# ESP32_EVKIT_v1_0.net
KiCad netlist of a schematic drawn in EAGLE
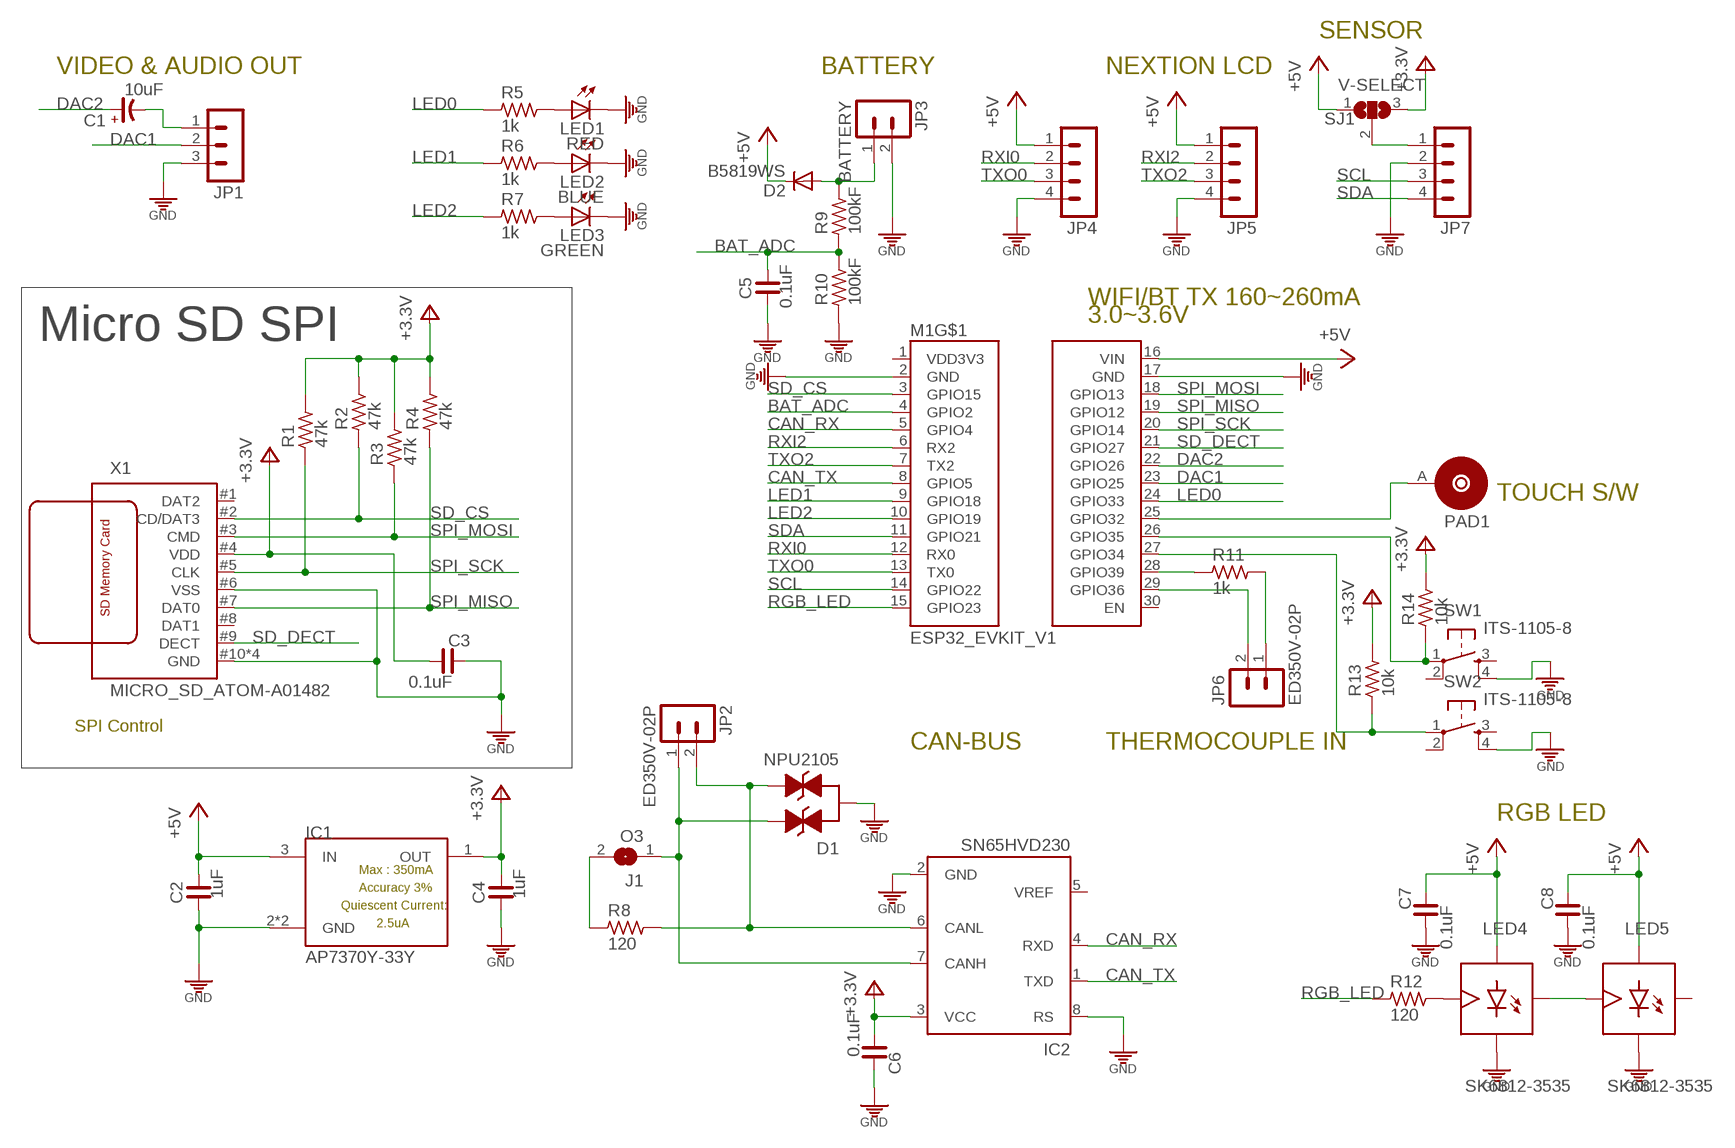
[diagram p0: schematic, sheet 1]

(export (version "E")
  (design (tool "Eeschema 10.0.6"))
  (components
    (comp (ref "C1")
      (value "10uF")
      (footprint "eagle-import:C2012_T")
      (libsource (lib "eagle-import") (part "CP_2012"))
    )
    (comp (ref "C2")
      (value "1uF")
      (footprint "eagle-import:C0603")
      (libsource (lib "eagle-import") (part "C_0603"))
    )
    (comp (ref "C3")
      (value "0.1uF")
      (footprint "eagle-import:C0603")
      (libsource (lib "eagle-import") (part "C_0603"))
    )
    (comp (ref "C4")
      (value "1uF")
      (footprint "eagle-import:C0603")
      (libsource (lib "eagle-import") (part "C_0603"))
    )
    (comp (ref "C5")
      (value "0.1uF")
      (footprint "eagle-import:C0603")
      (libsource (lib "eagle-import") (part "C_0603"))
    )
    (comp (ref "C6")
      (value "0.1uF")
      (footprint "eagle-import:C0603")
      (libsource (lib "eagle-import") (part "C_0603"))
    )
    (comp (ref "C7")
      (value "0.1uF")
      (footprint "eagle-import:C0603")
      (libsource (lib "eagle-import") (part "C_0603"))
    )
    (comp (ref "C8")
      (value "0.1uF")
      (footprint "eagle-import:C0603")
      (libsource (lib "eagle-import") (part "C_0603"))
    )
    (comp (ref "D1")
      (value "NPU2105")
      (footprint "eagle-import:SOT23@2")
      (libsource (lib "eagle-import") (part "NPU2105"))
    )
    (comp (ref "D2")
      (value "B5819WS")
      (footprint "eagle-import:SOD323-W")
      (libsource (lib "eagle-import") (part "B5189WWS"))
    )
    (comp (ref "IC1")
      (value "AP7370Y-33Y")
      (footprint "eagle-import:SOT89")
      (libsource (lib "eagle-import") (part "AP7370Y"))
    )
    (comp (ref "IC2")
      (value "SN65HVD230")
      (footprint "eagle-import:SO8")
      (libsource (lib "eagle-import") (part "PCA82C250T"))
    )
    (comp (ref "J1") (value "O3") (footprint "eagle-import:SJ") (libsource (lib "eagle-import") (part "SJ")))
    (comp (ref "JP1")
      (value "MA03-1DEF")
      (footprint "eagle-import:MA03")
      (libsource (lib "eagle-import") (part "MA03-1DEF"))
    )
    (comp (ref "JP2")
      (value "ED350V-02P")
      (footprint "eagle-import:ED350V-02P")
      (libsource (lib "eagle-import") (part "MA02ED350V-02P"))
    )
    (comp (ref "JP3")
      (value "BATTERY")
      (footprint "eagle-import:53398-02")
      (libsource (lib "eagle-import") (part "MA0253398"))
    )
    (comp (ref "JP4")
      (value "MA04-1SMALL")
      (footprint "eagle-import:MA04-1-S")
      (libsource (lib "eagle-import") (part "MA04-1SMALL"))
    )
    (comp (ref "JP5")
      (value "MA04-1SMALL")
      (footprint "eagle-import:MA04-1-S")
      (libsource (lib "eagle-import") (part "MA04-1SMALL"))
    )
    (comp (ref "JP6")
      (value "ED350V-02P")
      (footprint "eagle-import:ED350V-02P")
      (libsource (lib "eagle-import") (part "MA02ED350V-02P"))
    )
    (comp (ref "JP7")
      (value "MA04-1SMALL")
      (footprint "eagle-import:MA04-1-S")
      (libsource (lib "eagle-import") (part "MA04-1SMALL"))
    )
    (comp (ref "LED1")
      (value "RED")
      (footprint "eagle-import:LED-1608")
      (libsource (lib "eagle-import") (part "LEDSMD-1608"))
    )
    (comp (ref "LED2")
      (value "BLUE")
      (footprint "eagle-import:LED-1608")
      (libsource (lib "eagle-import") (part "LEDSMD-1608"))
    )
    (comp (ref "LED3")
      (value "GREEN")
      (footprint "eagle-import:LED-1608")
      (libsource (lib "eagle-import") (part "LEDSMD-1608"))
    )
    (comp (ref "LED4")
      (value "SK6812-3535")
      (footprint "eagle-import:LED3535")
      (libsource (lib "eagle-import") (part "SK68123535"))
    )
    (comp (ref "LED5")
      (value "SK6812-3535")
      (footprint "eagle-import:LED3535")
      (libsource (lib "eagle-import") (part "SK68123535"))
    )
    (comp (ref "M1")
      (value "ESP32_EVKIT_V1")
      (footprint "eagle-import:ESP32_DEVKIT_V1_DOIT")
      (libsource (lib "eagle-import") (part "ESP32_EVKIT_V1"))
    )
    (comp (ref "PAD1")
      (value "TOUCH_PAD01")
      (footprint "eagle-import:TOUCH_PAD1")
      (libsource (lib "eagle-import") (part "TOUCH_PAD01"))
    )
    (comp (ref "R1")
      (value "47k")
      (footprint "eagle-import:R0603")
      (libsource (lib "eagle-import") (part "R_0603"))
    )
    (comp (ref "R2")
      (value "47k")
      (footprint "eagle-import:R0603")
      (libsource (lib "eagle-import") (part "R_0603"))
    )
    (comp (ref "R3")
      (value "47k")
      (footprint "eagle-import:R0603")
      (libsource (lib "eagle-import") (part "R_0603"))
    )
    (comp (ref "R4")
      (value "47k")
      (footprint "eagle-import:R0603")
      (libsource (lib "eagle-import") (part "R_0603"))
    )
    (comp (ref "R5")
      (value "1k")
      (footprint "eagle-import:R0603")
      (libsource (lib "eagle-import") (part "R_0603"))
    )
    (comp (ref "R6")
      (value "1k")
      (footprint "eagle-import:R0603")
      (libsource (lib "eagle-import") (part "R_0603"))
    )
    (comp (ref "R7")
      (value "1k")
      (footprint "eagle-import:R0603")
      (libsource (lib "eagle-import") (part "R_0603"))
    )
    (comp (ref "R8")
      (value "120")
      (footprint "eagle-import:R0603")
      (libsource (lib "eagle-import") (part "R_0603"))
    )
    (comp (ref "R9")
      (value "100kF")
      (footprint "eagle-import:R0603")
      (libsource (lib "eagle-import") (part "R_0603"))
    )
    (comp (ref "R10")
      (value "100kF")
      (footprint "eagle-import:R0603")
      (libsource (lib "eagle-import") (part "R_0603"))
    )
    (comp (ref "R11")
      (value "1k")
      (footprint "eagle-import:R0603")
      (libsource (lib "eagle-import") (part "R_0603"))
    )
    (comp (ref "R12")
      (value "120")
      (footprint "eagle-import:R0603")
      (libsource (lib "eagle-import") (part "R_0603"))
    )
    (comp (ref "R13")
      (value "10k")
      (footprint "eagle-import:R0603")
      (libsource (lib "eagle-import") (part "R_0603"))
    )
    (comp (ref "R14")
      (value "10k")
      (footprint "eagle-import:R0603")
      (libsource (lib "eagle-import") (part "R_0603"))
    )
    (comp (ref "SJ1")
      (value "V-SELECT")
      (footprint "eagle-import:SJ_3")
      (libsource (lib "eagle-import") (part "SOLDERJUMPER_2WAYS"))
    )
    (comp (ref "SW1")
      (value "ITS-1105-8")
      (footprint "eagle-import:ITS-1105")
      (libsource (lib "eagle-import") (part "ITS-1105"))
    )
    (comp (ref "SW2")
      (value "ITS-1105-8")
      (footprint "eagle-import:ITS-1105")
      (libsource (lib "eagle-import") (part "ITS-1105"))
    )
    (comp (ref "X1")
      (value "MICRO_SD_ATOM-A01482")
      (footprint "eagle-import:ATOM-A01482")
      (libsource (lib "eagle-import") (part "MICRO_SD_ATOM-A01482"))
    )
  )
  (nets
    (net (code "1") (name "+3V3") (class "Default")
      (node (ref "C3") (pin "2") (pinfunction "2_2") (pintype "passive"))
      (node (ref "C4") (pin "1") (pinfunction "1_1") (pintype "passive"))
      (node (ref "C6") (pin "2") (pinfunction "2_2") (pintype "passive"))
      (node (ref "IC1") (pin "1") (pinfunction "OUT_1") (pintype "power_in"))
      (node (ref "IC2") (pin "3") (pinfunction "VCC_3") (pintype "power_in"))
      (node (ref "R1") (pin "2") (pinfunction "2_2") (pintype "passive"))
      (node (ref "R13") (pin "2") (pinfunction "2_2") (pintype "passive"))
      (node (ref "R14") (pin "2") (pinfunction "2_2") (pintype "passive"))
      (node (ref "R2") (pin "2") (pinfunction "2_2") (pintype "passive"))
      (node (ref "R3") (pin "2") (pinfunction "2_2") (pintype "passive"))
      (node (ref "R4") (pin "2") (pinfunction "2_2") (pintype "passive"))
      (node (ref "SJ1") (pin "3") (pinfunction "3_3") (pintype "passive"))
      (node (ref "X1") (pin "#4") (pinfunction "VDD_#4") (pintype "passive"))
    )
    (net (code "2") (name "+5V") (class "Default")
      (node (ref "C2") (pin "1") (pinfunction "1_1") (pintype "passive"))
      (node (ref "C7") (pin "1") (pinfunction "1_1") (pintype "passive"))
      (node (ref "C8") (pin "1") (pinfunction "1_1") (pintype "passive"))
      (node (ref "D2") (pin "C") (pinfunction "C_C") (pintype "passive"))
      (node (ref "IC1") (pin "3") (pinfunction "IN_3") (pintype "power_in"))
      (node (ref "JP4") (pin "1") (pinfunction "1_1") (pintype "passive"))
      (node (ref "JP5") (pin "1") (pinfunction "1_1") (pintype "passive"))
      (node (ref "LED4") (pin "4") (pinfunction "VDD_4") (pintype "power_in"))
      (node (ref "LED5") (pin "4") (pinfunction "VDD_4") (pintype "power_in"))
      (node (ref "M1") (pin "16") (pinfunction "VIN_16") (pintype "power_in"))
      (node (ref "SJ1") (pin "1") (pinfunction "1_1") (pintype "passive"))
    )
    (net (code "3") (name "/BAT_ADC") (class "Default")
      (node (ref "C5") (pin "1") (pinfunction "1_1") (pintype "passive"))
      (node (ref "M1") (pin "4") (pinfunction "GPIO2_4") (pintype "bidirectional"))
      (node (ref "R10") (pin "2") (pinfunction "2_2") (pintype "passive"))
      (node (ref "R9") (pin "1") (pinfunction "1_1") (pintype "passive"))
    )
    (net (code "4") (name "/CAN_RX") (class "Default")
      (node (ref "IC2") (pin "4") (pinfunction "RXD_4") (pintype "output"))
      (node (ref "M1") (pin "5") (pinfunction "GPIO4_5") (pintype "bidirectional"))
    )
    (net (code "5") (name "/CAN_TX") (class "Default")
      (node (ref "IC2") (pin "1") (pinfunction "TXD_1") (pintype "input"))
      (node (ref "M1") (pin "8") (pinfunction "GPIO5_8") (pintype "bidirectional"))
    )
    (net (code "6") (name "/DAC1") (class "Default")
      (node (ref "JP1") (pin "2") (pinfunction "2_2") (pintype "passive"))
      (node (ref "M1") (pin "23") (pinfunction "GPIO25_23") (pintype "bidirectional"))
    )
    (net (code "7") (name "/DAC2") (class "Default")
      (node (ref "C1") (pin "+") (pinfunction "+_+") (pintype "passive"))
      (node (ref "M1") (pin "22") (pinfunction "GPIO26_22") (pintype "bidirectional"))
    )
    (net (code "8") (name "/LED0") (class "Default")
      (node (ref "M1") (pin "24") (pinfunction "GPIO33_24") (pintype "bidirectional"))
      (node (ref "R5") (pin "1") (pinfunction "1_1") (pintype "passive"))
    )
    (net (code "9") (name "/LED1") (class "Default")
      (node (ref "M1") (pin "9") (pinfunction "GPIO18_9") (pintype "bidirectional"))
      (node (ref "R6") (pin "1") (pinfunction "1_1") (pintype "passive"))
    )
    (net (code "10") (name "/LED2") (class "Default")
      (node (ref "M1") (pin "10") (pinfunction "GPIO19_10") (pintype "bidirectional"))
      (node (ref "R7") (pin "1") (pinfunction "1_1") (pintype "passive"))
    )
    (net (code "11") (name "/RGB_LED") (class "Default")
      (node (ref "M1") (pin "15") (pinfunction "GPIO23_15") (pintype "bidirectional"))
      (node (ref "R12") (pin "1") (pinfunction "1_1") (pintype "passive"))
    )
    (net (code "12") (name "/RXI0") (class "Default")
      (node (ref "JP4") (pin "2") (pinfunction "2_2") (pintype "passive"))
      (node (ref "M1") (pin "12") (pinfunction "RX0_12") (pintype "bidirectional"))
    )
    (net (code "13") (name "/RXI2") (class "Default")
      (node (ref "JP5") (pin "2") (pinfunction "2_2") (pintype "passive"))
      (node (ref "M1") (pin "6") (pinfunction "RX2_6") (pintype "bidirectional"))
    )
    (net (code "14") (name "/SCL") (class "Default")
      (node (ref "JP7") (pin "3") (pinfunction "3_3") (pintype "passive"))
      (node (ref "M1") (pin "14") (pinfunction "GPIO22_14") (pintype "bidirectional"))
    )
    (net (code "15") (name "/SDA") (class "Default")
      (node (ref "JP7") (pin "4") (pinfunction "4_4") (pintype "passive"))
      (node (ref "M1") (pin "11") (pinfunction "GPIO21_11") (pintype "bidirectional"))
    )
    (net (code "16") (name "/SD_CS") (class "Default")
      (node (ref "M1") (pin "3") (pinfunction "GPIO15_3") (pintype "bidirectional"))
      (node (ref "R2") (pin "1") (pinfunction "1_1") (pintype "passive"))
      (node (ref "X1") (pin "#2") (pinfunction "CD/DAT3_#2") (pintype "passive"))
    )
    (net (code "17") (name "/SD_DECT") (class "Default")
      (node (ref "M1") (pin "21") (pinfunction "GPIO27_21") (pintype "bidirectional"))
      (node (ref "X1") (pin "#9") (pinfunction "DECT_#9") (pintype "passive"))
    )
    (net (code "18") (name "/SPI_MISO") (class "Default")
      (node (ref "M1") (pin "19") (pinfunction "GPIO12_19") (pintype "bidirectional"))
      (node (ref "R4") (pin "1") (pinfunction "1_1") (pintype "passive"))
      (node (ref "X1") (pin "#7") (pinfunction "DAT0_#7") (pintype "passive"))
    )
    (net (code "19") (name "/SPI_MOSI") (class "Default")
      (node (ref "M1") (pin "18") (pinfunction "GPIO13_18") (pintype "bidirectional"))
      (node (ref "R3") (pin "1") (pinfunction "1_1") (pintype "passive"))
      (node (ref "X1") (pin "#3") (pinfunction "CMD_#3") (pintype "passive"))
    )
    (net (code "20") (name "/SPI_SCK") (class "Default")
      (node (ref "M1") (pin "20") (pinfunction "GPIO14_20") (pintype "bidirectional"))
      (node (ref "R1") (pin "1") (pinfunction "1_1") (pintype "passive"))
      (node (ref "X1") (pin "#5") (pinfunction "CLK_#5") (pintype "passive"))
    )
    (net (code "21") (name "/TXO0") (class "Default")
      (node (ref "JP4") (pin "3") (pinfunction "3_3") (pintype "passive"))
      (node (ref "M1") (pin "13") (pinfunction "TX0_13") (pintype "bidirectional"))
    )
    (net (code "22") (name "/TXO2") (class "Default")
      (node (ref "JP5") (pin "3") (pinfunction "3_3") (pintype "passive"))
      (node (ref "M1") (pin "7") (pinfunction "TX2_7") (pintype "bidirectional"))
    )
    (net (code "23") (name "/VDD3V3") (class "Default")
      (node (ref "M1") (pin "1") (pinfunction "VDD3V3_1") (pintype "power_in"))
    )
    (net (code "24") (name "GND") (class "Default")
      (node (ref "C2") (pin "2") (pinfunction "2_2") (pintype "passive"))
      (node (ref "C3") (pin "1") (pinfunction "1_1") (pintype "passive"))
      (node (ref "C4") (pin "2") (pinfunction "2_2") (pintype "passive"))
      (node (ref "C5") (pin "2") (pinfunction "2_2") (pintype "passive"))
      (node (ref "C6") (pin "1") (pinfunction "1_1") (pintype "passive"))
      (node (ref "C7") (pin "2") (pinfunction "2_2") (pintype "passive"))
      (node (ref "C8") (pin "2") (pinfunction "2_2") (pintype "passive"))
      (node (ref "D1") (pin "D") (pinfunction "PIN3_D") (pintype "passive"))
      (node (ref "IC1") (pin "2") (pinfunction "GND_2") (pintype "power_in"))
      (node (ref "IC1") (pin "2@1") (pinfunction "GND_2@1") (pintype "power_in"))
      (node (ref "IC2") (pin "2") (pinfunction "GND_2") (pintype "power_in"))
      (node (ref "IC2") (pin "8") (pinfunction "RS_8") (pintype "input"))
      (node (ref "JP1") (pin "3") (pinfunction "3_3") (pintype "passive"))
      (node (ref "JP3") (pin "2") (pinfunction "2_2") (pintype "passive"))
      (node (ref "JP4") (pin "4") (pinfunction "4_4") (pintype "passive"))
      (node (ref "JP5") (pin "4") (pinfunction "4_4") (pintype "passive"))
      (node (ref "JP7") (pin "2") (pinfunction "2_2") (pintype "passive"))
      (node (ref "LED1") (pin "C") (pinfunction "C_C") (pintype "passive"))
      (node (ref "LED2") (pin "C") (pinfunction "C_C") (pintype "passive"))
      (node (ref "LED3") (pin "C") (pinfunction "C_C") (pintype "passive"))
      (node (ref "LED4") (pin "2") (pinfunction "VSS_2") (pintype "power_in"))
      (node (ref "LED5") (pin "2") (pinfunction "VSS_2") (pintype "power_in"))
      (node (ref "M1") (pin "17") (pinfunction "GND_17") (pintype "power_in"))
      (node (ref "M1") (pin "2") (pinfunction "GND_2") (pintype "power_in"))
      (node (ref "R10") (pin "1") (pinfunction "1_1") (pintype "passive"))
      (node (ref "SW1") (pin "4") (pinfunction "4_4") (pintype "passive"))
      (node (ref "SW2") (pin "4") (pinfunction "4_4") (pintype "passive"))
      (node (ref "X1") (pin "#10") (pinfunction "GND_#10") (pintype "passive"))
      (node (ref "X1") (pin "#10@") (pinfunction "GND_#10@") (pintype "passive"))
      (node (ref "X1") (pin "#10@1") (pinfunction "GND_#10@1") (pintype "passive"))
      (node (ref "X1") (pin "#13") (pinfunction "GND_#13") (pintype "passive"))
      (node (ref "X1") (pin "#6") (pinfunction "VSS_#6") (pintype "passive"))
    )
    (net (code "25") (name "Net-(C1-Pad-)") (class "Default")
      (node (ref "C1") (pin "-") (pinfunction "-_-") (pintype "passive"))
      (node (ref "JP1") (pin "1") (pinfunction "1_1") (pintype "passive"))
    )
    (net (code "26") (name "Net-(D1-PIN1)") (class "Default")
      (node (ref "D1") (pin "G") (pinfunction "PIN1_G") (pintype "passive"))
      (node (ref "IC2") (pin "7") (pinfunction "CANH_7") (pintype "bidirectional"))
      (node (ref "J1") (pin "1") (pinfunction "1_1") (pintype "passive"))
      (node (ref "JP2") (pin "1") (pinfunction "1_1") (pintype "passive"))
    )
    (net (code "27") (name "Net-(D1-PIN2)") (class "Default")
      (node (ref "D1") (pin "S") (pinfunction "PIN2_S") (pintype "passive"))
      (node (ref "IC2") (pin "6") (pinfunction "CANL_6") (pintype "bidirectional"))
      (node (ref "JP2") (pin "2") (pinfunction "2_2") (pintype "passive"))
      (node (ref "R8") (pin "2") (pinfunction "2_2") (pintype "passive"))
    )
    (net (code "28") (name "Net-(D2-PadA)") (class "Default")
      (node (ref "D2") (pin "A") (pinfunction "A_A") (pintype "passive"))
      (node (ref "JP3") (pin "1") (pinfunction "1_1") (pintype "passive"))
      (node (ref "R9") (pin "2") (pinfunction "2_2") (pintype "passive"))
    )
    (net (code "29") (name "Net-(J1-Pad2)") (class "Default")
      (node (ref "J1") (pin "2") (pinfunction "2_2") (pintype "passive"))
      (node (ref "R8") (pin "1") (pinfunction "1_1") (pintype "passive"))
    )
    (net (code "30") (name "Net-(JP6-Pad1)") (class "Default")
      (node (ref "JP6") (pin "1") (pinfunction "1_1") (pintype "passive"))
      (node (ref "R11") (pin "2") (pinfunction "2_2") (pintype "passive"))
    )
    (net (code "31") (name "Net-(JP7-Pad1)") (class "Default")
      (node (ref "JP7") (pin "1") (pinfunction "1_1") (pintype "passive"))
      (node (ref "SJ1") (pin "2") (pinfunction "2_2") (pintype "passive"))
    )
    (net (code "32") (name "Net-(LED1-PadA)") (class "Default")
      (node (ref "LED1") (pin "A") (pinfunction "A_A") (pintype "passive"))
      (node (ref "R5") (pin "2") (pinfunction "2_2") (pintype "passive"))
    )
    (net (code "33") (name "Net-(LED2-PadA)") (class "Default")
      (node (ref "LED2") (pin "A") (pinfunction "A_A") (pintype "passive"))
      (node (ref "R6") (pin "2") (pinfunction "2_2") (pintype "passive"))
    )
    (net (code "34") (name "Net-(LED3-PadA)") (class "Default")
      (node (ref "LED3") (pin "A") (pinfunction "A_A") (pintype "passive"))
      (node (ref "R7") (pin "2") (pinfunction "2_2") (pintype "passive"))
    )
    (net (code "35") (name "Net-(LED4-DIN)") (class "Default")
      (node (ref "LED4") (pin "3") (pinfunction "DIN_3") (pintype "input"))
      (node (ref "R12") (pin "2") (pinfunction "2_2") (pintype "passive"))
    )
    (net (code "36") (name "Net-(LED4-DOUT)") (class "Default")
      (node (ref "LED4") (pin "1") (pinfunction "DOUT_1") (pintype "output"))
      (node (ref "LED5") (pin "3") (pinfunction "DIN_3") (pintype "input"))
    )
    (net (code "37") (name "Net-(M1B-GPIO32)") (class "Default")
      (node (ref "M1") (pin "25") (pinfunction "GPIO32_25") (pintype "bidirectional"))
      (node (ref "PAD1") (pin "A") (pinfunction "2_A") (pintype "passive"))
    )
    (net (code "38") (name "Net-(M1B-GPIO34)") (class "Default")
      (node (ref "M1") (pin "27") (pinfunction "GPIO34_27") (pintype "input"))
      (node (ref "R13") (pin "1") (pinfunction "1_1") (pintype "passive"))
      (node (ref "SW2") (pin "1") (pinfunction "1_1") (pintype "passive"))
    )
    (net (code "39") (name "Net-(M1B-GPIO35)") (class "Default")
      (node (ref "M1") (pin "26") (pinfunction "GPIO35_26") (pintype "input"))
      (node (ref "R14") (pin "1") (pinfunction "1_1") (pintype "passive"))
      (node (ref "SW1") (pin "1") (pinfunction "1_1") (pintype "passive"))
    )
    (net (code "40") (name "Net-(M1B-GPIO36)") (class "Default")
      (node (ref "JP6") (pin "2") (pinfunction "2_2") (pintype "passive"))
      (node (ref "M1") (pin "29") (pinfunction "GPIO36_29") (pintype "input"))
    )
    (net (code "41") (name "Net-(M1B-GPIO39)") (class "Default")
      (node (ref "M1") (pin "28") (pinfunction "GPIO39_28") (pintype "input"))
      (node (ref "R11") (pin "1") (pinfunction "1_1") (pintype "passive"))
    )
    (net (code "42") (name "unconnected-(IC2-VREF-Pad5)") (class "Default")
      (node (ref "IC2") (pin "5") (pinfunction "VREF_5") (pintype "output"))
    )
    (net (code "43") (name "unconnected-(LED5-DOUT-Pad1)") (class "Default")
      (node (ref "LED5") (pin "1") (pinfunction "DOUT_1") (pintype "output"))
    )
    (net (code "44") (name "unconnected-(M1B-EN-Pad30)") (class "Default")
      (node (ref "M1") (pin "30") (pinfunction "EN_30") (pintype "input"))
    )
    (net (code "45") (name "unconnected-(SW1-Pad2)") (class "Default")
      (node (ref "SW1") (pin "2") (pinfunction "2_2") (pintype "passive"))
    )
    (net (code "46") (name "unconnected-(SW1-Pad3)") (class "Default")
      (node (ref "SW1") (pin "3") (pinfunction "3_3") (pintype "passive"))
    )
    (net (code "47") (name "unconnected-(SW2-Pad2)") (class "Default")
      (node (ref "SW2") (pin "2") (pinfunction "2_2") (pintype "passive"))
    )
    (net (code "48") (name "unconnected-(SW2-Pad3)") (class "Default")
      (node (ref "SW2") (pin "3") (pinfunction "3_3") (pintype "passive"))
    )
    (net (code "49") (name "unconnected-(X1-DAT1-Pad#8)") (class "Default")
      (node (ref "X1") (pin "#8") (pinfunction "DAT1_#8") (pintype "passive"))
    )
    (net (code "50") (name "unconnected-(X1-DAT2-Pad#1)") (class "Default")
      (node (ref "X1") (pin "#1") (pinfunction "DAT2_#1") (pintype "passive"))
    )
  )
)
